# ESP32_SENSORS.net
KiCad netlist of a schematic drawn in Altium Designer
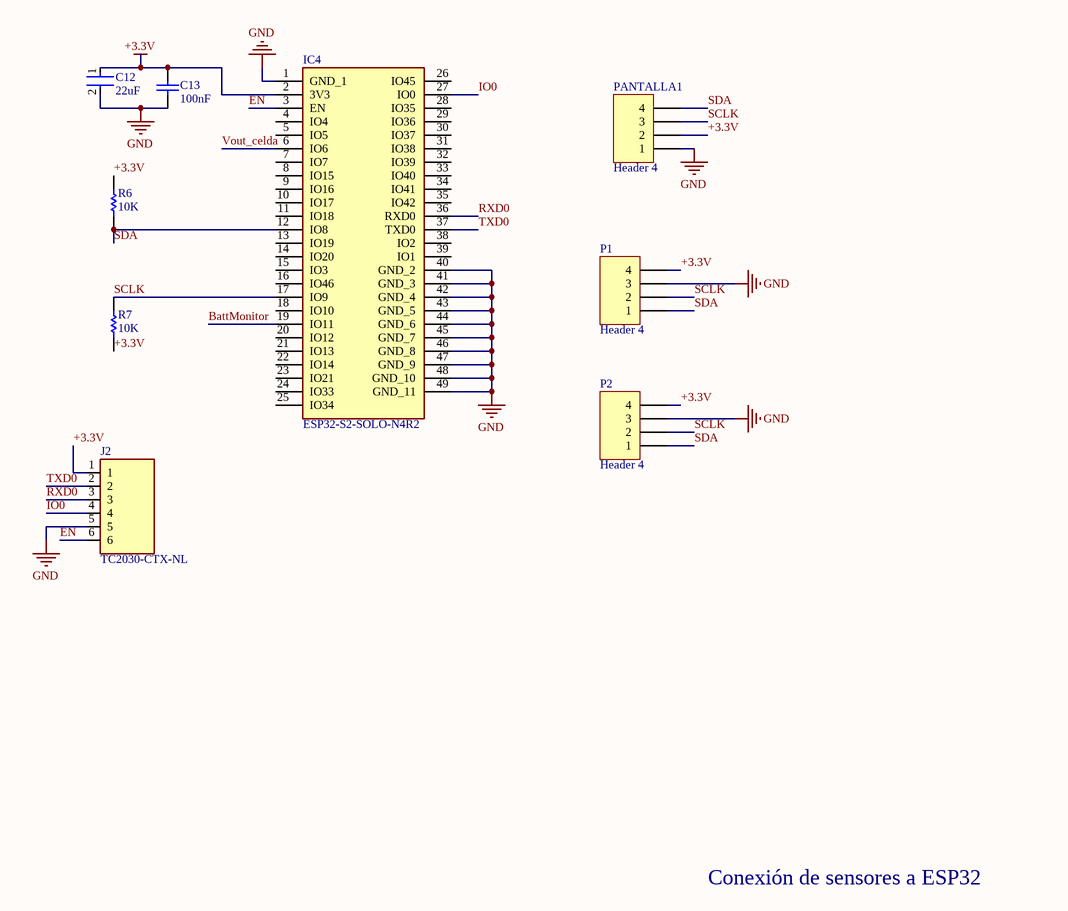
[diagram p0: ESP32_SENSORS.SchDoc]

(export (version "E")
  (design (tool "Eeschema 10.0.6"))
  (components
    (comp (ref "C12")
      (value "22uF")
      (footprint "FP-GRM188-0_2-IPC_C")
      (description "Chip Multilayer Ceramic Capacitors for General Purpose, 0603, 4.7uF, X5R, 15%, 10%, 35V")
      (fields (field (name "VOLTAGE") "35V") (field (name "TOLERANCE") "10%"))
      (libsource (lib "Altium Content Vault") (part "11868f565c42a9108669ba33697ecf6"))
    )
    (comp (ref "C13")
      (value "100nF")
      (footprint "CAPC1608X90X35NL10T15")
      (fields (field (name "MANUFACTURER") "Murata") (field (name "PART NUMBER") "GRM188F51E104ZA01D"))
      (libsource (lib "Altium Content Vault") (part "CAP"))
    )
    (comp (ref "IC4")
      (value "ESP32-S2-SOLO-N4R2")
      (footprint "SamacSys:ESP32S2SOLON4R2")
      (description "Integrated Circuit")
      (fields (field (name "MOUSER PART NUMBER") "356-ESP32-S2SOLON4R2"))
      (libsource (lib "*") (part "ESP32-S2-SOLO-N4R2"))
    )
    (comp (ref "J2")
      (value "TC2030-CTX-NL")
      (footprint "TC2030MCPNL10")
      (description "Connector")
      (fields (field (name "MANUFACTURER") "Tag Connect"))
      (libsource (lib "ESP32_SCALE") (part "TC2030-CTX-NL"))
    )
    (comp (ref "P1")
      (value "Header 4")
      (footprint "HDR1X4")
      (description "Header, 4-Pin")
      (fields (field (name "PUBLISHER") "Altium Limited"))
      (libsource (lib "Miscellaneous Connectors") (part "Header 4"))
    )
    (comp (ref "P2")
      (value "Header 4")
      (footprint "HDR1X4")
      (description "Header, 4-Pin")
      (fields (field (name "PUBLISHER") "Altium Limited"))
      (libsource (lib "Miscellaneous Connectors") (part "Header 4"))
    )
    (comp (ref "PANTALLA1")
      (value "Header 4")
      (footprint "HDR1X4")
      (description "Header, 4-Pin")
      (fields (field (name "PUBLISHER") "Altium Limited"))
      (libsource (lib "Miscellaneous Connectors") (part "Header 4"))
    )
    (comp (ref "R6")
      (value "10K")
      (footprint "RESC1609X55X30LL15T15")
      (description "Chip Resistor, 10 KOhm, +/- 1%, 0.1 W, -55 to 155 degC, 0603 (1608 Metric), RoHS, Tape and Reel")
      (fields (field (name "TOLERANCE") "1%") (field (name "MANUFACTURER") "Panasonic"))
      (libsource (lib "Altium Content Vault") (part "RES-2"))
    )
    (comp (ref "R7")
      (value "10K")
      (footprint "RESC1609X55X30LL15T15")
      (description "Chip Resistor, 10 KOhm, +/- 1%, 0.1 W, -55 to 155 degC, 0603 (1608 Metric), RoHS, Tape and Reel")
      (fields (field (name "TOLERANCE") "1%") (field (name "MANUFACTURER") "Panasonic"))
      (libsource (lib "Altium Content Vault") (part "RES-2"))
    )
  )
  (nets
    (net (code "1") (name "+3.3V") (class "Default")
      (node (ref "C12") (pin "1") (pinfunction "1_1") (pintype "passive"))
      (node (ref "C13") (pin "2") (pinfunction "2_2") (pintype "passive"))
      (node (ref "IC4") (pin "2") (pinfunction "3V3_2") (pintype "passive"))
      (node (ref "J2") (pin "1") (pinfunction "1_1") (pintype "passive"))
      (node (ref "P1") (pin "4") (pinfunction "4_4") (pintype "passive"))
      (node (ref "P2") (pin "4") (pinfunction "4_4") (pintype "passive"))
      (node (ref "PANTALLA1") (pin "2") (pinfunction "2_2") (pintype "passive"))
      (node (ref "R6") (pin "1") (pinfunction "1_1") (pintype "passive"))
      (node (ref "R7") (pin "1") (pinfunction "1_1") (pintype "passive"))
    )
    (net (code "2") (name "/BattMonitor") (class "Default")
      (node (ref "IC4") (pin "19") (pinfunction "IO11_19") (pintype "passive"))
    )
    (net (code "3") (name "/EN") (class "Default")
      (node (ref "IC4") (pin "3") (pinfunction "EN_3") (pintype "passive"))
      (node (ref "J2") (pin "6") (pinfunction "6_6") (pintype "passive"))
    )
    (net (code "4") (name "/IO0") (class "Default")
      (node (ref "IC4") (pin "27") (pinfunction "IO0_27") (pintype "passive"))
      (node (ref "J2") (pin "4") (pinfunction "4_4") (pintype "passive"))
    )
    (net (code "5") (name "/RXD0") (class "Default")
      (node (ref "IC4") (pin "36") (pinfunction "RXD0_36") (pintype "passive"))
      (node (ref "J2") (pin "3") (pinfunction "3_3") (pintype "passive"))
    )
    (net (code "6") (name "/SCLK") (class "Default")
      (node (ref "IC4") (pin "17") (pinfunction "IO9_17") (pintype "passive"))
      (node (ref "P1") (pin "2") (pinfunction "2_2") (pintype "passive"))
      (node (ref "P2") (pin "2") (pinfunction "2_2") (pintype "passive"))
      (node (ref "PANTALLA1") (pin "3") (pinfunction "3_3") (pintype "passive"))
      (node (ref "R7") (pin "2") (pinfunction "2_2") (pintype "passive"))
    )
    (net (code "7") (name "/SDA") (class "Default")
      (node (ref "IC4") (pin "12") (pinfunction "IO8_12") (pintype "passive"))
      (node (ref "P1") (pin "1") (pinfunction "1_1") (pintype "passive"))
      (node (ref "P2") (pin "1") (pinfunction "1_1") (pintype "passive"))
      (node (ref "PANTALLA1") (pin "4") (pinfunction "4_4") (pintype "passive"))
      (node (ref "R6") (pin "2") (pinfunction "2_2") (pintype "passive"))
    )
    (net (code "8") (name "/TXD0") (class "Default")
      (node (ref "IC4") (pin "37") (pinfunction "TXD0_37") (pintype "passive"))
      (node (ref "J2") (pin "2") (pinfunction "2_2") (pintype "passive"))
    )
    (net (code "9") (name "/Vout_celda") (class "Default")
      (node (ref "IC4") (pin "6") (pinfunction "IO6_6") (pintype "passive"))
    )
    (net (code "10") (name "GND") (class "Default")
      (node (ref "C12") (pin "2") (pinfunction "2_2") (pintype "passive"))
      (node (ref "C13") (pin "1") (pinfunction "1_1") (pintype "passive"))
      (node (ref "IC4") (pin "1") (pinfunction "GND_1_1") (pintype "passive"))
      (node (ref "IC4") (pin "40") (pinfunction "GND_2_40") (pintype "passive"))
      (node (ref "IC4") (pin "41") (pinfunction "GND_3_41") (pintype "passive"))
      (node (ref "IC4") (pin "42") (pinfunction "GND_4_42") (pintype "passive"))
      (node (ref "IC4") (pin "43") (pinfunction "GND_5_43") (pintype "passive"))
      (node (ref "IC4") (pin "44") (pinfunction "GND_6_44") (pintype "passive"))
      (node (ref "IC4") (pin "45") (pinfunction "GND_7_45") (pintype "passive"))
      (node (ref "IC4") (pin "46") (pinfunction "GND_8_46") (pintype "passive"))
      (node (ref "IC4") (pin "47") (pinfunction "GND_9_47") (pintype "passive"))
      (node (ref "IC4") (pin "48") (pinfunction "GND_10_48") (pintype "passive"))
      (node (ref "IC4") (pin "49") (pinfunction "GND_11_49") (pintype "passive"))
      (node (ref "J2") (pin "5") (pinfunction "5_5") (pintype "passive"))
      (node (ref "P1") (pin "3") (pinfunction "3_3") (pintype "passive"))
      (node (ref "P2") (pin "3") (pinfunction "3_3") (pintype "passive"))
      (node (ref "PANTALLA1") (pin "1") (pinfunction "1_1") (pintype "passive"))
    )
    (net (code "11") (name "unconnected-(IC4-IO1-Pad39)") (class "Default")
      (node (ref "IC4") (pin "39") (pinfunction "IO1_39") (pintype "passive"))
    )
    (net (code "12") (name "unconnected-(IC4-IO2-Pad38)") (class "Default")
      (node (ref "IC4") (pin "38") (pinfunction "IO2_38") (pintype "passive"))
    )
    (net (code "13") (name "unconnected-(IC4-IO3-Pad15)") (class "Default")
      (node (ref "IC4") (pin "15") (pinfunction "IO3_15") (pintype "passive"))
    )
    (net (code "14") (name "unconnected-(IC4-IO4-Pad4)") (class "Default")
      (node (ref "IC4") (pin "4") (pinfunction "IO4_4") (pintype "passive"))
    )
    (net (code "15") (name "unconnected-(IC4-IO5-Pad5)") (class "Default")
      (node (ref "IC4") (pin "5") (pinfunction "IO5_5") (pintype "passive"))
    )
    (net (code "16") (name "unconnected-(IC4-IO7-Pad7)") (class "Default")
      (node (ref "IC4") (pin "7") (pinfunction "IO7_7") (pintype "passive"))
    )
    (net (code "17") (name "unconnected-(IC4-IO10-Pad18)") (class "Default")
      (node (ref "IC4") (pin "18") (pinfunction "IO10_18") (pintype "passive"))
    )
    (net (code "18") (name "unconnected-(IC4-IO12-Pad20)") (class "Default")
      (node (ref "IC4") (pin "20") (pinfunction "IO12_20") (pintype "passive"))
    )
    (net (code "19") (name "unconnected-(IC4-IO13-Pad21)") (class "Default")
      (node (ref "IC4") (pin "21") (pinfunction "IO13_21") (pintype "passive"))
    )
    (net (code "20") (name "unconnected-(IC4-IO14-Pad22)") (class "Default")
      (node (ref "IC4") (pin "22") (pinfunction "IO14_22") (pintype "passive"))
    )
    (net (code "21") (name "unconnected-(IC4-IO15-Pad8)") (class "Default")
      (node (ref "IC4") (pin "8") (pinfunction "IO15_8") (pintype "passive"))
    )
    (net (code "22") (name "unconnected-(IC4-IO16-Pad9)") (class "Default")
      (node (ref "IC4") (pin "9") (pinfunction "IO16_9") (pintype "passive"))
    )
    (net (code "23") (name "unconnected-(IC4-IO17-Pad10)") (class "Default")
      (node (ref "IC4") (pin "10") (pinfunction "IO17_10") (pintype "passive"))
    )
    (net (code "24") (name "unconnected-(IC4-IO18-Pad11)") (class "Default")
      (node (ref "IC4") (pin "11") (pinfunction "IO18_11") (pintype "passive"))
    )
    (net (code "25") (name "unconnected-(IC4-IO19-Pad13)") (class "Default")
      (node (ref "IC4") (pin "13") (pinfunction "IO19_13") (pintype "passive"))
    )
    (net (code "26") (name "unconnected-(IC4-IO20-Pad14)") (class "Default")
      (node (ref "IC4") (pin "14") (pinfunction "IO20_14") (pintype "passive"))
    )
    (net (code "27") (name "unconnected-(IC4-IO21-Pad23)") (class "Default")
      (node (ref "IC4") (pin "23") (pinfunction "IO21_23") (pintype "passive"))
    )
    (net (code "28") (name "unconnected-(IC4-IO33-Pad24)") (class "Default")
      (node (ref "IC4") (pin "24") (pinfunction "IO33_24") (pintype "passive"))
    )
    (net (code "29") (name "unconnected-(IC4-IO34-Pad25)") (class "Default")
      (node (ref "IC4") (pin "25") (pinfunction "IO34_25") (pintype "passive"))
    )
    (net (code "30") (name "unconnected-(IC4-IO35-Pad28)") (class "Default")
      (node (ref "IC4") (pin "28") (pinfunction "IO35_28") (pintype "passive"))
    )
    (net (code "31") (name "unconnected-(IC4-IO36-Pad29)") (class "Default")
      (node (ref "IC4") (pin "29") (pinfunction "IO36_29") (pintype "passive"))
    )
    (net (code "32") (name "unconnected-(IC4-IO37-Pad30)") (class "Default")
      (node (ref "IC4") (pin "30") (pinfunction "IO37_30") (pintype "passive"))
    )
    (net (code "33") (name "unconnected-(IC4-IO38-Pad31)") (class "Default")
      (node (ref "IC4") (pin "31") (pinfunction "IO38_31") (pintype "passive"))
    )
    (net (code "34") (name "unconnected-(IC4-IO39-Pad32)") (class "Default")
      (node (ref "IC4") (pin "32") (pinfunction "IO39_32") (pintype "passive"))
    )
    (net (code "35") (name "unconnected-(IC4-IO40-Pad33)") (class "Default")
      (node (ref "IC4") (pin "33") (pinfunction "IO40_33") (pintype "passive"))
    )
    (net (code "36") (name "unconnected-(IC4-IO41-Pad34)") (class "Default")
      (node (ref "IC4") (pin "34") (pinfunction "IO41_34") (pintype "passive"))
    )
    (net (code "37") (name "unconnected-(IC4-IO42-Pad35)") (class "Default")
      (node (ref "IC4") (pin "35") (pinfunction "IO42_35") (pintype "passive"))
    )
    (net (code "38") (name "unconnected-(IC4-IO45-Pad26)") (class "Default")
      (node (ref "IC4") (pin "26") (pinfunction "IO45_26") (pintype "passive"))
    )
    (net (code "39") (name "unconnected-(IC4-IO46-Pad16)") (class "Default")
      (node (ref "IC4") (pin "16") (pinfunction "IO46_16") (pintype "passive"))
    )
  )
)
